# digital_io.net
KiCad netlist of a schematic drawn in Altium Designer
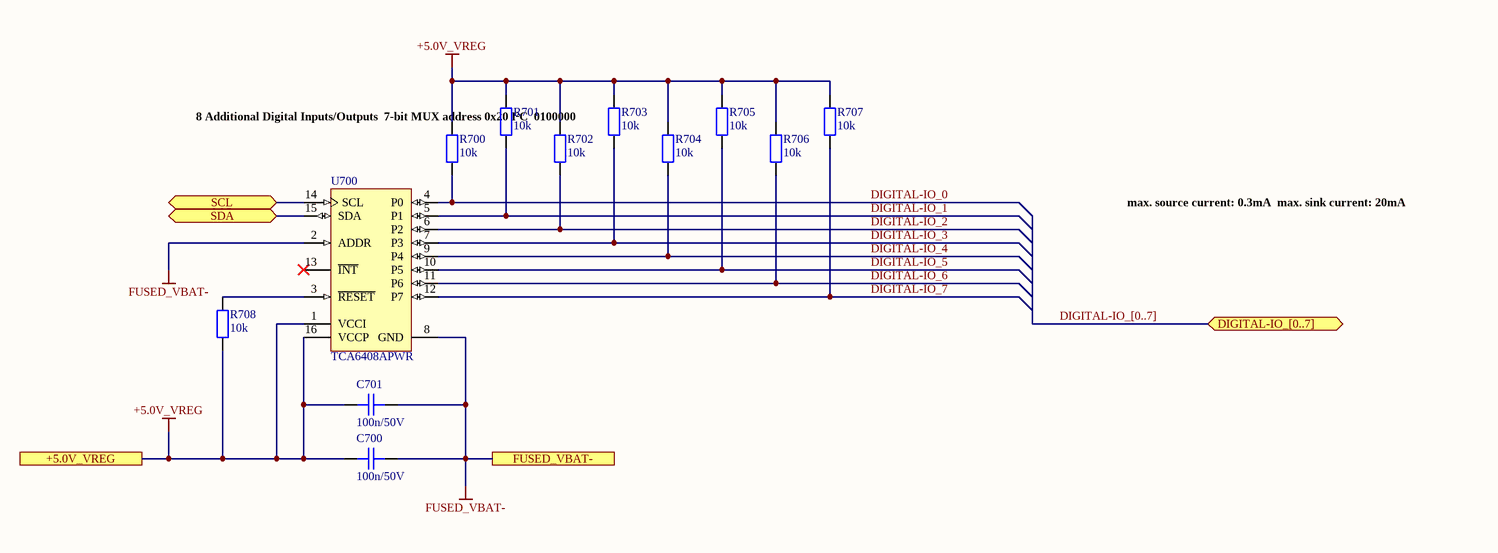
[diagram p0: digital_io.SchDoc]

(export (version "E")
  (design (tool "Eeschema 10.0.6"))
  (components
    (comp (ref "C700")
      (value "100n/50V")
      (footprint "CAPC1608X08N")
      (description "MLCC")
      (fields (field (name "PART NUMBER") "gen_C_ceramic_100n_50V_X7R_0603"))
      (libsource (lib "OE750") (part "C"))
    )
    (comp (ref "C701")
      (value "100n/50V")
      (footprint "CAPC1608X08N")
      (description "MLCC")
      (fields (field (name "PART NUMBER") "gen_C_ceramic_100n_50V_X7R_0603"))
      (libsource (lib "OE750") (part "C"))
    )
    (comp (ref "R700")
      (value "10k")
      (footprint "RESC1608X05N")
      (description "SMD Resistor 10k 0603")
      (fields (field (name "PART NUMBER") "gen_R_10k_0603") (field (name "TOLERANCE") "1%"))
      (libsource (lib "OE750") (part "R"))
    )
    (comp (ref "R701")
      (value "10k")
      (footprint "RESC1608X05N")
      (description "SMD Resistor 10k 0603")
      (fields (field (name "PART NUMBER") "gen_R_10k_0603") (field (name "TOLERANCE") "1%"))
      (libsource (lib "OE750") (part "R"))
    )
    (comp (ref "R702")
      (value "10k")
      (footprint "RESC1608X05N")
      (description "SMD Resistor 10k 0603")
      (fields (field (name "PART NUMBER") "gen_R_10k_0603") (field (name "TOLERANCE") "1%"))
      (libsource (lib "OE750") (part "R"))
    )
    (comp (ref "R703")
      (value "10k")
      (footprint "RESC1608X05N")
      (description "SMD Resistor 10k 0603")
      (fields (field (name "PART NUMBER") "gen_R_10k_0603") (field (name "TOLERANCE") "1%"))
      (libsource (lib "OE750") (part "R"))
    )
    (comp (ref "R704")
      (value "10k")
      (footprint "RESC1608X05N")
      (description "SMD Resistor 10k 0603")
      (fields (field (name "PART NUMBER") "gen_R_10k_0603") (field (name "TOLERANCE") "1%"))
      (libsource (lib "OE750") (part "R"))
    )
    (comp (ref "R705")
      (value "10k")
      (footprint "RESC1608X05N")
      (description "SMD Resistor 10k 0603")
      (fields (field (name "PART NUMBER") "gen_R_10k_0603") (field (name "TOLERANCE") "1%"))
      (libsource (lib "OE750") (part "R"))
    )
    (comp (ref "R706")
      (value "10k")
      (footprint "RESC1608X05N")
      (description "SMD Resistor 10k 0603")
      (fields (field (name "PART NUMBER") "gen_R_10k_0603") (field (name "TOLERANCE") "1%"))
      (libsource (lib "OE750") (part "R"))
    )
    (comp (ref "R707")
      (value "10k")
      (footprint "RESC1608X05N")
      (description "SMD Resistor 10k 0603")
      (fields (field (name "PART NUMBER") "gen_R_10k_0603") (field (name "TOLERANCE") "1%"))
      (libsource (lib "OE750") (part "R"))
    )
    (comp (ref "R708")
      (value "10k")
      (footprint "RESC1608X05N")
      (description "SMD Resistor 10k 0603")
      (fields (field (name "PART NUMBER") "gen_R_10k_0603") (field (name "TOLERANCE") "1%"))
      (libsource (lib "OE750") (part "R"))
    )
    (comp (ref "U700")
      (value "TCA6408APWR")
      (footprint "PW0016A_L")
      (fields (field (name "MANUFACTURER") "Texas Instruments"))
      (libsource (lib "Altium Content Vault") (part "TI-TCA6408A-TSSOP_PW-16"))
    )
  )
  (nets
    (net (code "1") (name "+5.0V_VREG") (class "Default")
      (node (ref "C700") (pin "2") (pinfunction "2_2") (pintype "passive"))
      (node (ref "C701") (pin "2") (pinfunction "2_2") (pintype "passive"))
      (node (ref "R700") (pin "2") (pinfunction "2_2") (pintype "passive"))
      (node (ref "R701") (pin "2") (pinfunction "2_2") (pintype "passive"))
      (node (ref "R702") (pin "2") (pinfunction "2_2") (pintype "passive"))
      (node (ref "R703") (pin "2") (pinfunction "2_2") (pintype "passive"))
      (node (ref "R704") (pin "2") (pinfunction "2_2") (pintype "passive"))
      (node (ref "R705") (pin "2") (pinfunction "2_2") (pintype "passive"))
      (node (ref "R706") (pin "2") (pinfunction "2_2") (pintype "passive"))
      (node (ref "R707") (pin "2") (pinfunction "2_2") (pintype "passive"))
      (node (ref "R708") (pin "1") (pinfunction "1_1") (pintype "passive"))
      (node (ref "U700") (pin "1") (pinfunction "VCCI_1") (pintype "power_in"))
      (node (ref "U700") (pin "16") (pinfunction "VCCP_16") (pintype "power_in"))
    )
    (net (code "2") (name "/DIGITAL-IO_0") (class "Default")
      (node (ref "R700") (pin "1") (pinfunction "1_1") (pintype "passive"))
      (node (ref "U700") (pin "4") (pinfunction "P0_4") (pintype "bidirectional"))
    )
    (net (code "3") (name "/DIGITAL-IO_1") (class "Default")
      (node (ref "R701") (pin "1") (pinfunction "1_1") (pintype "passive"))
      (node (ref "U700") (pin "5") (pinfunction "P1_5") (pintype "bidirectional"))
    )
    (net (code "4") (name "/DIGITAL-IO_2") (class "Default")
      (node (ref "R702") (pin "1") (pinfunction "1_1") (pintype "passive"))
      (node (ref "U700") (pin "6") (pinfunction "P2_6") (pintype "bidirectional"))
    )
    (net (code "5") (name "/DIGITAL-IO_3") (class "Default")
      (node (ref "R703") (pin "1") (pinfunction "1_1") (pintype "passive"))
      (node (ref "U700") (pin "7") (pinfunction "P3_7") (pintype "bidirectional"))
    )
    (net (code "6") (name "/DIGITAL-IO_4") (class "Default")
      (node (ref "R704") (pin "1") (pinfunction "1_1") (pintype "passive"))
      (node (ref "U700") (pin "9") (pinfunction "P4_9") (pintype "bidirectional"))
    )
    (net (code "7") (name "/DIGITAL-IO_5") (class "Default")
      (node (ref "R705") (pin "1") (pinfunction "1_1") (pintype "passive"))
      (node (ref "U700") (pin "10") (pinfunction "P5_10") (pintype "bidirectional"))
    )
    (net (code "8") (name "/DIGITAL-IO_6") (class "Default")
      (node (ref "R706") (pin "1") (pinfunction "1_1") (pintype "passive"))
      (node (ref "U700") (pin "11") (pinfunction "P6_11") (pintype "bidirectional"))
    )
    (net (code "9") (name "/DIGITAL-IO_7") (class "Default")
      (node (ref "R707") (pin "1") (pinfunction "1_1") (pintype "passive"))
      (node (ref "U700") (pin "12") (pinfunction "P7_12") (pintype "bidirectional"))
    )
    (net (code "11") (name "/SCL") (class "Default")
      (node (ref "U700") (pin "14") (pinfunction "SCL_14") (pintype "input"))
    )
    (net (code "12") (name "/SDA") (class "Default")
      (node (ref "U700") (pin "15") (pinfunction "SDA_15") (pintype "bidirectional"))
    )
    (net (code "13") (name "FUSED_VBAT-") (class "Default")
      (node (ref "C700") (pin "1") (pinfunction "1_1") (pintype "passive"))
      (node (ref "C701") (pin "1") (pinfunction "1_1") (pintype "passive"))
      (node (ref "U700") (pin "2") (pinfunction "ADDR_2") (pintype "input"))
      (node (ref "U700") (pin "8") (pinfunction "GND_8") (pintype "power_in"))
    )
    (net (code "14") (name "Net-(U700-~{RESET})") (class "Default")
      (node (ref "R708") (pin "2") (pinfunction "2_2") (pintype "passive"))
      (node (ref "U700") (pin "3") (pinfunction "~{RESET}_3") (pintype "input"))
    )
    (net (code "15") (name "unconnected-(U700-~{INT}-Pad13)") (class "Default")
      (node (ref "U700") (pin "13") (pinfunction "~{INT}_13") (pintype "open_collector+no_connect"))
    )
  )
)
